# Rov_Kumanda_v2.net
KiCad netlist of a schematic drawn in Altium Designer
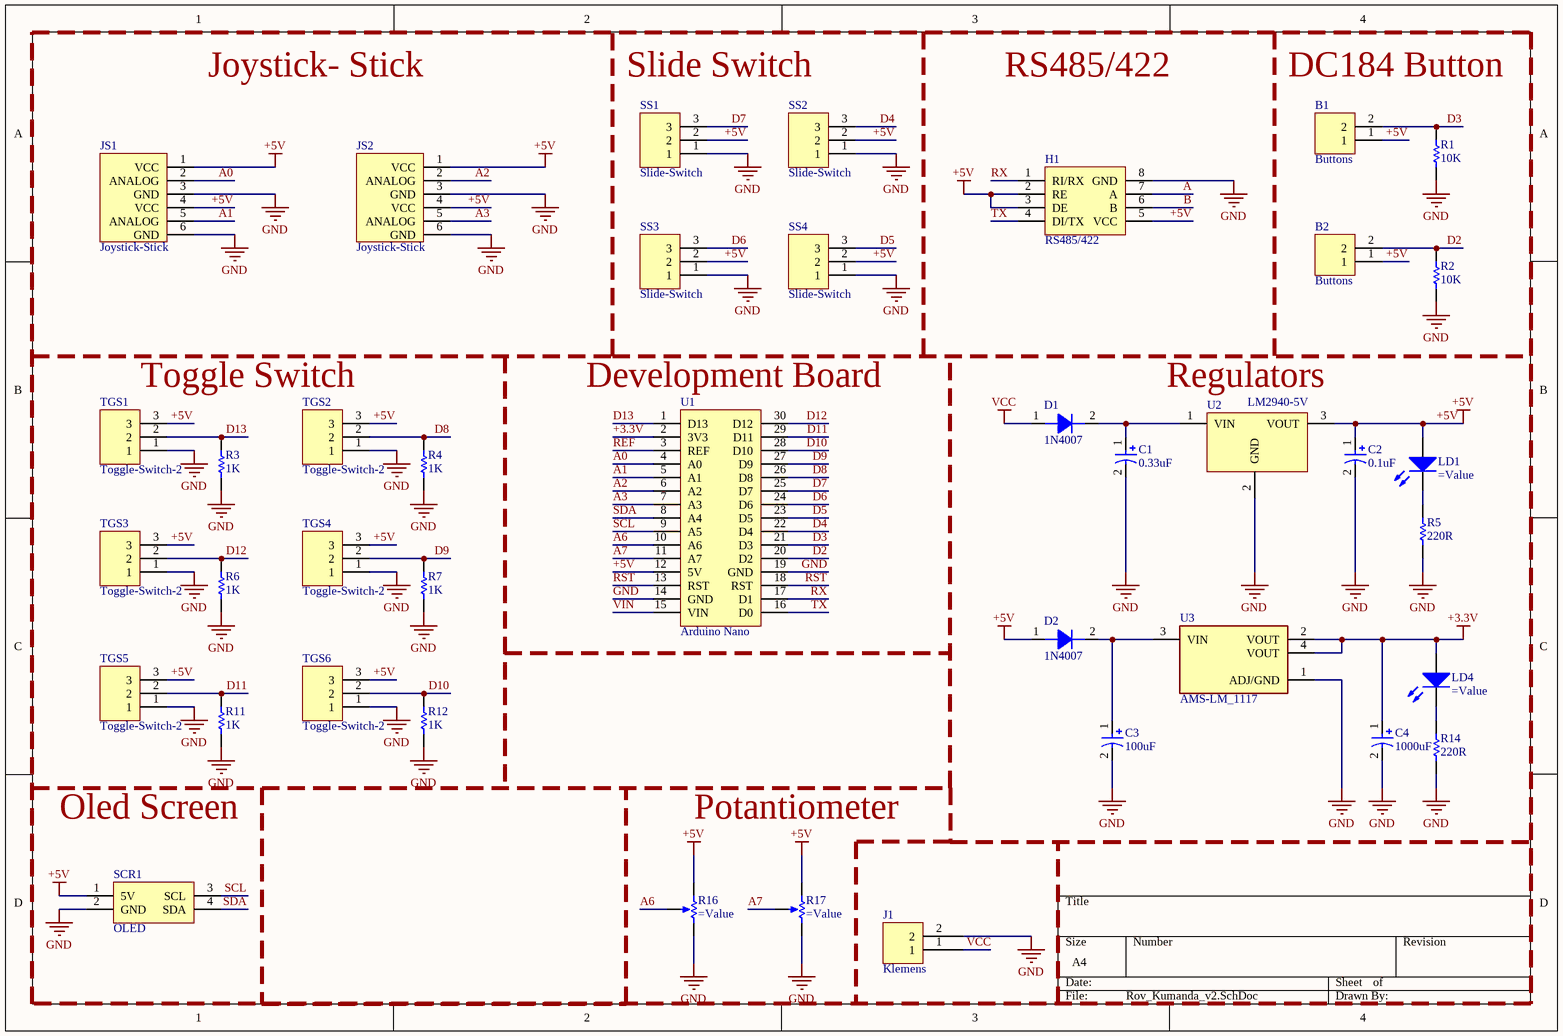
[diagram p0: Rov_Kumanda_v2.SchDoc]

(export (version "E")
  (design (tool "Eeschema 10.0.6"))
  (components
    (comp (ref "B1") (value "Buttons") (footprint "Buttons") (libsource (lib "Buttons") (part "Buttons")))
    (comp (ref "B2") (value "Buttons") (footprint "Buttons") (libsource (lib "Buttons") (part "Buttons")))
    (comp (ref "C1")
      (value "0.33uF")
      (footprint "PolarizedCap")
      (description "Cap Alum 0.33UF 20% 50V Radial")
      (fields
        (field (name "MANUFACTURER PART NUMBER") "UMA1HR33MDD1TP")
        (field (name "MANUFACTURER") "Nichicon")
      )
      (libsource (lib "MyDatabaseLib") (part "Capacitor POL"))
    )
    (comp (ref "C2")
      (value "0.1uF")
      (footprint "PolarizedCap")
      (description "Cap Alum 0.33UF 20% 50V Radial")
      (fields
        (field (name "MANUFACTURER PART NUMBER") "UMA1HR33MDD1TP")
        (field (name "MANUFACTURER") "Nichicon")
      )
      (libsource (lib "MyDatabaseLib") (part "Capacitor POL"))
    )
    (comp (ref "C3")
      (value "100uF")
      (footprint "PolarizedCap")
      (description "Cap Alum 0.33UF 20% 50V Radial")
      (fields
        (field (name "MANUFACTURER PART NUMBER") "UMA1HR33MDD1TP")
        (field (name "MANUFACTURER") "Nichicon")
      )
      (libsource (lib "MyDatabaseLib") (part "Capacitor POL"))
    )
    (comp (ref "C4")
      (value "1000uF")
      (footprint "PolarizedCap")
      (description "Cap Alum 0.33UF 20% 50V Radial")
      (fields
        (field (name "MANUFACTURER PART NUMBER") "UMA1HR33MDD1TP")
        (field (name "MANUFACTURER") "Nichicon")
      )
      (libsource (lib "MyDatabaseLib") (part "Capacitor POL"))
    )
    (comp (ref "D1")
      (value "1N4007")
      (footprint "THT")
      (description "Diode 1KV 1A 2-Pin DO-41 T/R")
      (fields (field (name "MANUFACTURER") "ON Semiconductor / Fairchild"))
      (libsource (lib "MyDatabaseLib") (part "Diode"))
    )
    (comp (ref "D2")
      (value "1N4007")
      (footprint "THT")
      (description "Diode 1KV 1A 2-Pin DO-41 T/R")
      (fields (field (name "MANUFACTURER") "ON Semiconductor / Fairchild"))
      (libsource (lib "MyDatabaseLib") (part "Diode"))
    )
    (comp (ref "H1")
      (value "RS485/422")
      (footprint "RS485/422")
      (libsource (lib "RS485_422") (part "RS485/422"))
    )
    (comp (ref "J1")
      (value "Klemens")
      (footprint "klemens_3.5mm")
      (libsource (lib "klemens") (part "Klemens"))
    )
    (comp (ref "JS1")
      (value "Joystick-Stick")
      (footprint "Joystick-Stick")
      (fields (field (name "MANUFACTURER PART NUMBER") "THB001P") (field (name "MANUFACTURER") "ITT C&K"))
      (libsource (lib "MyDatabaseLib") (part "Joystick-Stick"))
    )
    (comp (ref "JS2")
      (value "Joystick-Stick")
      (footprint "Joystick-Stick")
      (fields (field (name "MANUFACTURER PART NUMBER") "THB001P") (field (name "MANUFACTURER") "ITT C&K"))
      (libsource (lib "MyDatabaseLib") (part "Joystick-Stick"))
    )
    (comp (ref "LD1")
      (value "~")
      (footprint "THT_LED")
      (description "LED 3 mm (T1) red, 151031SS06000, Würth Elektronik")
      (fields
        (field (name "MANUFACTURER PART NUMBER") "151031SS06000")
        (field (name "MANUFACTURER") "Wurth Electronics")
      )
      (libsource (lib "MyDatabaseLib") (part "LED"))
    )
    (comp (ref "LD4")
      (value "~")
      (footprint "THT_LED")
      (description "LED 3 mm (T1) red, 151031SS06000, Würth Elektronik")
      (fields
        (field (name "MANUFACTURER PART NUMBER") "151031SS06000")
        (field (name "MANUFACTURER") "Wurth Electronics")
      )
      (libsource (lib "MyDatabaseLib") (part "LED"))
    )
    (comp (ref "R1")
      (value "10K")
      (footprint "THT_Resistor")
      (description "MBA0204 M/F Res,  0.4W 50PPM 1% 220R")
      (fields
        (field (name "MANUFACTURER PART NUMBER") "MBA02040C2200FC100")
        (field (name "MANUFACTURER") "Vishay Beyschlag")
      )
      (libsource (lib "MyDatabaseLib") (part "Res1"))
    )
    (comp (ref "R2")
      (value "10K")
      (footprint "THT_Resistor")
      (description "MBA0204 M/F Res,  0.4W 50PPM 1% 220R")
      (fields
        (field (name "MANUFACTURER PART NUMBER") "MBA02040C2200FC100")
        (field (name "MANUFACTURER") "Vishay Beyschlag")
      )
      (libsource (lib "MyDatabaseLib") (part "Res1"))
    )
    (comp (ref "R3")
      (value "1K")
      (footprint "THT_Resistor")
      (description "MBA0204 M/F Res,  0.4W 50PPM 1% 220R")
      (fields
        (field (name "MANUFACTURER PART NUMBER") "MBA02040C2200FC100")
        (field (name "MANUFACTURER") "Vishay Beyschlag")
      )
      (libsource (lib "MyDatabaseLib") (part "Res1"))
    )
    (comp (ref "R4")
      (value "1K")
      (footprint "THT_Resistor")
      (description "MBA0204 M/F Res,  0.4W 50PPM 1% 220R")
      (fields
        (field (name "MANUFACTURER PART NUMBER") "MBA02040C2200FC100")
        (field (name "MANUFACTURER") "Vishay Beyschlag")
      )
      (libsource (lib "MyDatabaseLib") (part "Res1"))
    )
    (comp (ref "R5")
      (value "220R")
      (footprint "THT_Resistor")
      (description "MBA0204 M/F Res,  0.4W 50PPM 1% 220R")
      (fields
        (field (name "MANUFACTURER PART NUMBER") "MBA02040C2200FC100")
        (field (name "MANUFACTURER") "Vishay Beyschlag")
      )
      (libsource (lib "MyDatabaseLib") (part "Res1"))
    )
    (comp (ref "R6")
      (value "1K")
      (footprint "THT_Resistor")
      (description "MBA0204 M/F Res,  0.4W 50PPM 1% 220R")
      (fields
        (field (name "MANUFACTURER PART NUMBER") "MBA02040C2200FC100")
        (field (name "MANUFACTURER") "Vishay Beyschlag")
      )
      (libsource (lib "MyDatabaseLib") (part "Res1"))
    )
    (comp (ref "R7")
      (value "1K")
      (footprint "THT_Resistor")
      (description "MBA0204 M/F Res,  0.4W 50PPM 1% 220R")
      (fields
        (field (name "MANUFACTURER PART NUMBER") "MBA02040C2200FC100")
        (field (name "MANUFACTURER") "Vishay Beyschlag")
      )
      (libsource (lib "MyDatabaseLib") (part "Res1"))
    )
    (comp (ref "R11")
      (value "1K")
      (footprint "THT_Resistor")
      (description "MBA0204 M/F Res,  0.4W 50PPM 1% 220R")
      (fields
        (field (name "MANUFACTURER PART NUMBER") "MBA02040C2200FC100")
        (field (name "MANUFACTURER") "Vishay Beyschlag")
      )
      (libsource (lib "MyDatabaseLib") (part "Res1"))
    )
    (comp (ref "R12")
      (value "1K")
      (footprint "THT_Resistor")
      (description "MBA0204 M/F Res,  0.4W 50PPM 1% 220R")
      (fields
        (field (name "MANUFACTURER PART NUMBER") "MBA02040C2200FC100")
        (field (name "MANUFACTURER") "Vishay Beyschlag")
      )
      (libsource (lib "MyDatabaseLib") (part "Res1"))
    )
    (comp (ref "R14")
      (value "220R")
      (footprint "THT_Resistor")
      (description "MBA0204 M/F Res,  0.4W 50PPM 1% 220R")
      (fields
        (field (name "MANUFACTURER PART NUMBER") "MBA02040C2200FC100")
        (field (name "MANUFACTURER") "Vishay Beyschlag")
      )
      (libsource (lib "MyDatabaseLib") (part "Res1"))
    )
    (comp (ref "R16")
      (value "~")
      (footprint "THT_Potantiometer")
      (description "Potentiometers 100ohms 20% Round Linear Res.")
      (fields (field (name "MANUFACTURER PART NUMBER") "026TB32R101B1A1") (field (name "MANUFACTURER") "CTS"))
      (libsource (lib "MyDatabaseLib") (part "RPot"))
    )
    (comp (ref "R17")
      (value "~")
      (footprint "THT_Potantiometer")
      (description "Potentiometers 100ohms 20% Round Linear Res.")
      (fields (field (name "MANUFACTURER PART NUMBER") "026TB32R101B1A1") (field (name "MANUFACTURER") "CTS"))
      (libsource (lib "MyDatabaseLib") (part "RPot"))
    )
    (comp (ref "SCR1")
      (value "OLED")
      (footprint "128*64_OLED")
      (description "Lcd Graphic 84X48 Nokia 5110")
      (fields (field (name "MANUFACTURER PART NUMBER") "LCD-10168") (field (name "MANUFACTURER") "SparkFun"))
      (libsource (lib "MyDatabaseLib") (part "OLED"))
    )
    (comp (ref "SS1")
      (value "Slide-Switch")
      (footprint "Slide_Switch")
      (description "C & K COMPONENTS - JS202011SCQN - SWITCH, DPDT, 0.6A, 6VDC, SMD")
      (fields
        (field (name "MANUFACTURER PART NUMBER") "JS202011SCQN")
        (field (name "MANUFACTURER") "ITT C&K")
      )
      (libsource (lib "MyDatabaseLib") (part "Slide-Switch"))
    )
    (comp (ref "SS2")
      (value "Slide-Switch")
      (footprint "Slide_Switch")
      (description "C & K COMPONENTS - JS202011SCQN - SWITCH, DPDT, 0.6A, 6VDC, SMD")
      (fields
        (field (name "MANUFACTURER PART NUMBER") "JS202011SCQN")
        (field (name "MANUFACTURER") "ITT C&K")
      )
      (libsource (lib "MyDatabaseLib") (part "Slide-Switch"))
    )
    (comp (ref "SS3")
      (value "Slide-Switch")
      (footprint "Slide_Switch")
      (description "C & K COMPONENTS - JS202011SCQN - SWITCH, DPDT, 0.6A, 6VDC, SMD")
      (fields
        (field (name "MANUFACTURER PART NUMBER") "JS202011SCQN")
        (field (name "MANUFACTURER") "ITT C&K")
      )
      (libsource (lib "MyDatabaseLib") (part "Slide-Switch"))
    )
    (comp (ref "SS4")
      (value "Slide-Switch")
      (footprint "Slide_Switch")
      (description "C & K COMPONENTS - JS202011SCQN - SWITCH, DPDT, 0.6A, 6VDC, SMD")
      (fields
        (field (name "MANUFACTURER PART NUMBER") "JS202011SCQN")
        (field (name "MANUFACTURER") "ITT C&K")
      )
      (libsource (lib "MyDatabaseLib") (part "Slide-Switch"))
    )
    (comp (ref "TGS1")
      (value "Toggle-Switch-2")
      (footprint "Toggle_Switch")
      (description "E-SWITCH - 100SP1T1B4M2QE - SWITCH, TOGGLE, SPDT, 5A, 120VAC, 28VDC")
      (fields
        (field (name "MANUFACTURER PART NUMBER") "100SP1T1B4M2QE")
        (field (name "MANUFACTURER") "E-Switch")
      )
      (libsource (lib "MyDatabaseLib") (part "Toggle-Switch-2"))
    )
    (comp (ref "TGS2")
      (value "Toggle-Switch-2")
      (footprint "Toggle_Switch")
      (description "E-SWITCH - 100SP1T1B4M2QE - SWITCH, TOGGLE, SPDT, 5A, 120VAC, 28VDC")
      (fields
        (field (name "MANUFACTURER PART NUMBER") "100SP1T1B4M2QE")
        (field (name "MANUFACTURER") "E-Switch")
      )
      (libsource (lib "MyDatabaseLib") (part "Toggle-Switch-2"))
    )
    (comp (ref "TGS3")
      (value "Toggle-Switch-2")
      (footprint "Toggle_Switch")
      (description "E-SWITCH - 100SP1T1B4M2QE - SWITCH, TOGGLE, SPDT, 5A, 120VAC, 28VDC")
      (fields
        (field (name "MANUFACTURER PART NUMBER") "100SP1T1B4M2QE")
        (field (name "MANUFACTURER") "E-Switch")
      )
      (libsource (lib "MyDatabaseLib") (part "Toggle-Switch-2"))
    )
    (comp (ref "TGS4")
      (value "Toggle-Switch-2")
      (footprint "Toggle_Switch")
      (description "E-SWITCH - 100SP1T1B4M2QE - SWITCH, TOGGLE, SPDT, 5A, 120VAC, 28VDC")
      (fields
        (field (name "MANUFACTURER PART NUMBER") "100SP1T1B4M2QE")
        (field (name "MANUFACTURER") "E-Switch")
      )
      (libsource (lib "MyDatabaseLib") (part "Toggle-Switch-2"))
    )
    (comp (ref "TGS5")
      (value "Toggle-Switch-2")
      (footprint "Toggle_Switch")
      (description "E-SWITCH - 100SP1T1B4M2QE - SWITCH, TOGGLE, SPDT, 5A, 120VAC, 28VDC")
      (fields
        (field (name "MANUFACTURER PART NUMBER") "100SP1T1B4M2QE")
        (field (name "MANUFACTURER") "E-Switch")
      )
      (libsource (lib "MyDatabaseLib") (part "Toggle-Switch-2"))
    )
    (comp (ref "TGS6")
      (value "Toggle-Switch-2")
      (footprint "Toggle_Switch")
      (description "E-SWITCH - 100SP1T1B4M2QE - SWITCH, TOGGLE, SPDT, 5A, 120VAC, 28VDC")
      (fields
        (field (name "MANUFACTURER PART NUMBER") "100SP1T1B4M2QE")
        (field (name "MANUFACTURER") "E-Switch")
      )
      (libsource (lib "MyDatabaseLib") (part "Toggle-Switch-2"))
    )
    (comp (ref "U1")
      (value "Arduino Nano")
      (footprint "Arduino-Nano")
      (fields (field (name "MANUFACTURER PART NUMBER") "A000005") (field (name "MANUFACTURER") "Arduino"))
      (libsource (lib "MyDatabaseLib") (part "Arduino Nano"))
    )
    (comp (ref "U2")
      (value "LM2940-5V")
      (footprint "TO220")
      (description "Series 3-Terminal Positive Regulators")
      (fields
        (field (name "MANUFACTURER PART NUMBER") "LM7805CT/NOPB")
        (field (name "MANUFACTURER") "Texas Instruments")
      )
      (libsource (lib "MyDatabaseLib") (part "LM2940-5V"))
    )
    (comp (ref "U3")
      (value "AMS-LM_1117")
      (footprint "SOT223")
      (fields
        (field (name "MANUFACTURER PART NUMBER") "LM1117IMPX-5.0/NOPB")
        (field (name "MANUFACTURER") "TI National Semiconductor")
      )
      (libsource (lib "MyDatabaseLib") (part "AMS-LM_1117"))
    )
  )
  (nets
    (net (code "1") (name "+3.3V") (class "Default")
      (node (ref "C4") (pin "1") (pinfunction "P_1") (pintype "passive"))
      (node (ref "LD4") (pin "2") (pinfunction "A_2") (pintype "passive"))
      (node (ref "U1") (pin "2") (pinfunction "3V3_2") (pintype "passive"))
      (node (ref "U3") (pin "2") (pinfunction "VOUT_2") (pintype "passive"))
      (node (ref "U3") (pin "4") (pinfunction "VOUT_4") (pintype "passive"))
    )
    (net (code "2") (name "+5V") (class "Default")
      (node (ref "B1") (pin "1") (pinfunction "1_1") (pintype "passive"))
      (node (ref "B2") (pin "1") (pinfunction "1_1") (pintype "passive"))
      (node (ref "C2") (pin "1") (pinfunction "P_1") (pintype "passive"))
      (node (ref "D2") (pin "1") (pinfunction "A_1") (pintype "passive"))
      (node (ref "H1") (pin "2") (pinfunction "RE_2") (pintype "passive"))
      (node (ref "H1") (pin "3") (pinfunction "DE_3") (pintype "passive"))
      (node (ref "H1") (pin "5") (pinfunction "VCC_5") (pintype "passive"))
      (node (ref "JS1") (pin "1") (pinfunction "VCC_1") (pintype "passive"))
      (node (ref "JS1") (pin "4") (pinfunction "VCC_4") (pintype "passive"))
      (node (ref "JS2") (pin "1") (pinfunction "VCC_1") (pintype "passive"))
      (node (ref "JS2") (pin "4") (pinfunction "VCC_4") (pintype "passive"))
      (node (ref "LD1") (pin "2") (pinfunction "A_2") (pintype "passive"))
      (node (ref "R16") (pin "1") (pinfunction "TOP_1") (pintype "passive"))
      (node (ref "R17") (pin "1") (pinfunction "TOP_1") (pintype "passive"))
      (node (ref "SCR1") (pin "1") (pinfunction "5V_1") (pintype "passive"))
      (node (ref "SS1") (pin "2") (pinfunction "2_2") (pintype "passive"))
      (node (ref "SS2") (pin "2") (pinfunction "2_2") (pintype "passive"))
      (node (ref "SS3") (pin "2") (pinfunction "2_2") (pintype "passive"))
      (node (ref "SS4") (pin "2") (pinfunction "2_2") (pintype "passive"))
      (node (ref "TGS1") (pin "3") (pinfunction "3_3") (pintype "passive"))
      (node (ref "TGS2") (pin "3") (pinfunction "3_3") (pintype "passive"))
      (node (ref "TGS3") (pin "3") (pinfunction "3_3") (pintype "passive"))
      (node (ref "TGS4") (pin "3") (pinfunction "3_3") (pintype "passive"))
      (node (ref "TGS5") (pin "3") (pinfunction "3_3") (pintype "passive"))
      (node (ref "TGS6") (pin "3") (pinfunction "3_3") (pintype "passive"))
      (node (ref "U1") (pin "12") (pinfunction "5V_12") (pintype "passive"))
      (node (ref "U2") (pin "3") (pinfunction "VOUT_3") (pintype "passive"))
    )
    (net (code "3") (name "/A") (class "Default")
      (node (ref "H1") (pin "7") (pinfunction "A_7") (pintype "passive"))
    )
    (net (code "4") (name "/A0") (class "Default")
      (node (ref "JS1") (pin "2") (pinfunction "ANALOG_2") (pintype "passive"))
      (node (ref "U1") (pin "4") (pinfunction "A0_4") (pintype "passive"))
    )
    (net (code "5") (name "/A1") (class "Default")
      (node (ref "JS1") (pin "5") (pinfunction "ANALOG_5") (pintype "passive"))
      (node (ref "U1") (pin "5") (pinfunction "A1_5") (pintype "passive"))
    )
    (net (code "6") (name "/A2") (class "Default")
      (node (ref "JS2") (pin "2") (pinfunction "ANALOG_2") (pintype "passive"))
      (node (ref "U1") (pin "6") (pinfunction "A2_6") (pintype "passive"))
    )
    (net (code "7") (name "/A3") (class "Default")
      (node (ref "JS2") (pin "5") (pinfunction "ANALOG_5") (pintype "passive"))
      (node (ref "U1") (pin "7") (pinfunction "A3_7") (pintype "passive"))
    )
    (net (code "8") (name "/A6") (class "Default")
      (node (ref "R16") (pin "3") (pinfunction "TAP_3") (pintype "passive"))
      (node (ref "U1") (pin "10") (pinfunction "A6_10") (pintype "passive"))
    )
    (net (code "9") (name "/A7") (class "Default")
      (node (ref "R17") (pin "3") (pinfunction "TAP_3") (pintype "passive"))
      (node (ref "U1") (pin "11") (pinfunction "A7_11") (pintype "passive"))
    )
    (net (code "10") (name "/B") (class "Default")
      (node (ref "H1") (pin "6") (pinfunction "B_6") (pintype "passive"))
    )
    (net (code "11") (name "/D2") (class "Default")
      (node (ref "B2") (pin "2") (pinfunction "2_2") (pintype "passive"))
      (node (ref "R2") (pin "2") (pinfunction "2_2") (pintype "passive"))
      (node (ref "U1") (pin "20") (pinfunction "D2_20") (pintype "passive"))
    )
    (net (code "12") (name "/D3") (class "Default")
      (node (ref "B1") (pin "2") (pinfunction "2_2") (pintype "passive"))
      (node (ref "R1") (pin "2") (pinfunction "2_2") (pintype "passive"))
      (node (ref "U1") (pin "21") (pinfunction "D3_21") (pintype "passive"))
    )
    (net (code "13") (name "/D4") (class "Default")
      (node (ref "SS2") (pin "3") (pinfunction "3_3") (pintype "passive"))
      (node (ref "U1") (pin "22") (pinfunction "D4_22") (pintype "passive"))
    )
    (net (code "14") (name "/D5") (class "Default")
      (node (ref "SS4") (pin "3") (pinfunction "3_3") (pintype "passive"))
      (node (ref "U1") (pin "23") (pinfunction "D5_23") (pintype "passive"))
    )
    (net (code "15") (name "/D6") (class "Default")
      (node (ref "SS3") (pin "3") (pinfunction "3_3") (pintype "passive"))
      (node (ref "U1") (pin "24") (pinfunction "D6_24") (pintype "passive"))
    )
    (net (code "16") (name "/D7") (class "Default")
      (node (ref "SS1") (pin "3") (pinfunction "3_3") (pintype "passive"))
      (node (ref "U1") (pin "25") (pinfunction "D7_25") (pintype "passive"))
    )
    (net (code "17") (name "/D8") (class "Default")
      (node (ref "R4") (pin "2") (pinfunction "2_2") (pintype "passive"))
      (node (ref "TGS2") (pin "2") (pinfunction "2_2") (pintype "passive"))
      (node (ref "U1") (pin "26") (pinfunction "D8_26") (pintype "passive"))
    )
    (net (code "18") (name "/D9") (class "Default")
      (node (ref "R7") (pin "2") (pinfunction "2_2") (pintype "passive"))
      (node (ref "TGS4") (pin "2") (pinfunction "2_2") (pintype "passive"))
      (node (ref "U1") (pin "27") (pinfunction "D9_27") (pintype "passive"))
    )
    (net (code "19") (name "/D10") (class "Default")
      (node (ref "R12") (pin "2") (pinfunction "2_2") (pintype "passive"))
      (node (ref "TGS6") (pin "2") (pinfunction "2_2") (pintype "passive"))
      (node (ref "U1") (pin "28") (pinfunction "D10_28") (pintype "passive"))
    )
    (net (code "20") (name "/D11") (class "Default")
      (node (ref "R11") (pin "2") (pinfunction "2_2") (pintype "passive"))
      (node (ref "TGS5") (pin "2") (pinfunction "2_2") (pintype "passive"))
      (node (ref "U1") (pin "29") (pinfunction "D11_29") (pintype "passive"))
    )
    (net (code "21") (name "/D12") (class "Default")
      (node (ref "R6") (pin "2") (pinfunction "2_2") (pintype "passive"))
      (node (ref "TGS3") (pin "2") (pinfunction "2_2") (pintype "passive"))
      (node (ref "U1") (pin "30") (pinfunction "D12_30") (pintype "passive"))
    )
    (net (code "22") (name "/D13") (class "Default")
      (node (ref "R3") (pin "2") (pinfunction "2_2") (pintype "passive"))
      (node (ref "TGS1") (pin "2") (pinfunction "2_2") (pintype "passive"))
      (node (ref "U1") (pin "1") (pinfunction "D13_1") (pintype "passive"))
    )
    (net (code "23") (name "/REF") (class "Default")
      (node (ref "U1") (pin "3") (pinfunction "REF_3") (pintype "passive"))
    )
    (net (code "24") (name "/RST") (class "Default")
      (node (ref "U1") (pin "13") (pinfunction "RST_13") (pintype "passive"))
      (node (ref "U1") (pin "18") (pinfunction "RST_18") (pintype "passive"))
    )
    (net (code "25") (name "/RX") (class "Default")
      (node (ref "H1") (pin "1") (pinfunction "RI/RX_1") (pintype "passive"))
      (node (ref "U1") (pin "17") (pinfunction "D1_17") (pintype "passive"))
    )
    (net (code "26") (name "/SCL") (class "Default")
      (node (ref "SCR1") (pin "3") (pinfunction "SCL_3") (pintype "passive"))
      (node (ref "U1") (pin "9") (pinfunction "A5_9") (pintype "passive"))
    )
    (net (code "27") (name "/SDA") (class "Default")
      (node (ref "SCR1") (pin "4") (pinfunction "SDA_4") (pintype "passive"))
      (node (ref "U1") (pin "8") (pinfunction "A4_8") (pintype "passive"))
    )
    (net (code "28") (name "/TX") (class "Default")
      (node (ref "H1") (pin "4") (pinfunction "DI/TX_4") (pintype "passive"))
      (node (ref "U1") (pin "16") (pinfunction "D0_16") (pintype "passive"))
    )
    (net (code "29") (name "/VIN") (class "Default")
      (node (ref "U1") (pin "15") (pinfunction "VIN_15") (pintype "passive"))
    )
    (net (code "30") (name "GND") (class "Default")
      (node (ref "C1") (pin "2") (pinfunction "N_2") (pintype "passive"))
      (node (ref "C2") (pin "2") (pinfunction "N_2") (pintype "passive"))
      (node (ref "C3") (pin "2") (pinfunction "N_2") (pintype "passive"))
      (node (ref "C4") (pin "2") (pinfunction "N_2") (pintype "passive"))
      (node (ref "H1") (pin "8") (pinfunction "GND_8") (pintype "passive"))
      (node (ref "J1") (pin "2") (pinfunction "2_2") (pintype "passive"))
      (node (ref "JS1") (pin "3") (pinfunction "GND_3") (pintype "passive"))
      (node (ref "JS1") (pin "6") (pinfunction "GND_6") (pintype "passive"))
      (node (ref "JS2") (pin "3") (pinfunction "GND_3") (pintype "passive"))
      (node (ref "JS2") (pin "6") (pinfunction "GND_6") (pintype "passive"))
      (node (ref "R1") (pin "1") (pinfunction "1_1") (pintype "passive"))
      (node (ref "R11") (pin "1") (pinfunction "1_1") (pintype "passive"))
      (node (ref "R12") (pin "1") (pinfunction "1_1") (pintype "passive"))
      (node (ref "R14") (pin "1") (pinfunction "1_1") (pintype "passive"))
      (node (ref "R16") (pin "2") (pinfunction "BOT_2") (pintype "passive"))
      (node (ref "R17") (pin "2") (pinfunction "BOT_2") (pintype "passive"))
      (node (ref "R2") (pin "1") (pinfunction "1_1") (pintype "passive"))
      (node (ref "R3") (pin "1") (pinfunction "1_1") (pintype "passive"))
      (node (ref "R4") (pin "1") (pinfunction "1_1") (pintype "passive"))
      (node (ref "R5") (pin "1") (pinfunction "1_1") (pintype "passive"))
      (node (ref "R6") (pin "1") (pinfunction "1_1") (pintype "passive"))
      (node (ref "R7") (pin "1") (pinfunction "1_1") (pintype "passive"))
      (node (ref "SCR1") (pin "2") (pinfunction "GND_2") (pintype "passive"))
      (node (ref "SS1") (pin "1") (pinfunction "1_1") (pintype "passive"))
      (node (ref "SS2") (pin "1") (pinfunction "1_1") (pintype "passive"))
      (node (ref "SS3") (pin "1") (pinfunction "1_1") (pintype "passive"))
      (node (ref "SS4") (pin "1") (pinfunction "1_1") (pintype "passive"))
      (node (ref "TGS1") (pin "1") (pinfunction "1_1") (pintype "passive"))
      (node (ref "TGS2") (pin "1") (pinfunction "1_1") (pintype "passive"))
      (node (ref "TGS3") (pin "1") (pinfunction "1_1") (pintype "passive"))
      (node (ref "TGS4") (pin "1") (pinfunction "1_1") (pintype "passive"))
      (node (ref "TGS5") (pin "1") (pinfunction "1_1") (pintype "passive"))
      (node (ref "TGS6") (pin "1") (pinfunction "1_1") (pintype "passive"))
      (node (ref "U1") (pin "14") (pinfunction "GND_14") (pintype "passive"))
      (node (ref "U1") (pin "19") (pinfunction "GND_19") (pintype "passive"))
      (node (ref "U2") (pin "2") (pinfunction "GND_2") (pintype "passive"))
      (node (ref "U3") (pin "1") (pinfunction "ADJ/GND_1") (pintype "passive"))
    )
    (net (code "31") (name "Net-(C1-P)") (class "Default")
      (node (ref "C1") (pin "1") (pinfunction "P_1") (pintype "passive"))
      (node (ref "D1") (pin "2") (pinfunction "K_2") (pintype "passive"))
      (node (ref "U2") (pin "1") (pinfunction "VIN_1") (pintype "passive"))
    )
    (net (code "32") (name "Net-(C3-P)") (class "Default")
      (node (ref "C3") (pin "1") (pinfunction "P_1") (pintype "passive"))
      (node (ref "D2") (pin "2") (pinfunction "K_2") (pintype "passive"))
      (node (ref "U3") (pin "3") (pinfunction "VIN_3") (pintype "passive"))
    )
    (net (code "33") (name "Net-(LD1-K)") (class "Default")
      (node (ref "LD1") (pin "1") (pinfunction "K_1") (pintype "passive"))
      (node (ref "R5") (pin "2") (pinfunction "2_2") (pintype "passive"))
    )
    (net (code "34") (name "Net-(LD4-K)") (class "Default")
      (node (ref "LD4") (pin "1") (pinfunction "K_1") (pintype "passive"))
      (node (ref "R14") (pin "2") (pinfunction "2_2") (pintype "passive"))
    )
    (net (code "35") (name "VCC") (class "Default")
      (node (ref "D1") (pin "1") (pinfunction "A_1") (pintype "passive"))
      (node (ref "J1") (pin "1") (pinfunction "1_1") (pintype "passive"))
    )
  )
)
